# 5V-25V_to_12V3A_DC-DC_Converter.net
KiCad netlist of a schematic drawn in Altium Designer
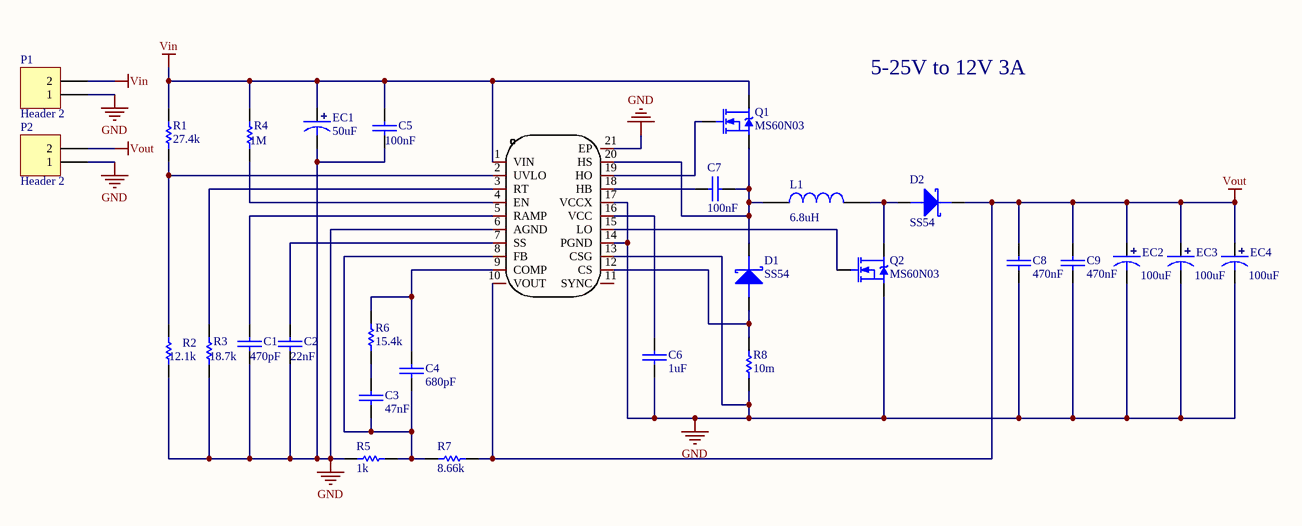
[diagram p0: 5V-25V to 12V3A DC-DC Converter.SchDoc]

(export (version "E")
  (design (tool "Eeschema 10.0.6"))
  (components
    (comp (ref "C1")
      (value "470pF")
      (footprint "0402C")
      (description "无极性电容")
      (libsource (lib "电容") (part "CAP"))
    )
    (comp (ref "C2")
      (value "22nF")
      (footprint "0402C")
      (description "无极性电容")
      (libsource (lib "电容") (part "CAP"))
    )
    (comp (ref "C3")
      (value "47nF")
      (footprint "0402C")
      (description "无极性电容")
      (libsource (lib "电容") (part "CAP"))
    )
    (comp (ref "C4")
      (value "680pF")
      (footprint "0402C")
      (description "无极性电容")
      (libsource (lib "电容") (part "CAP"))
    )
    (comp (ref "C5")
      (value "100nF")
      (footprint "0402C")
      (description "无极性电容")
      (libsource (lib "电容") (part "CAP"))
    )
    (comp (ref "C6")
      (value "1uF")
      (footprint "0402C")
      (description "无极性电容")
      (libsource (lib "电容") (part "CAP"))
    )
    (comp (ref "C7")
      (value "100nF")
      (footprint "0402C")
      (description "无极性电容")
      (libsource (lib "电容") (part "CAP"))
    )
    (comp (ref "C8")
      (value "470nF")
      (footprint "0402C")
      (description "无极性电容")
      (libsource (lib "电容") (part "CAP"))
    )
    (comp (ref "C9")
      (value "470nF")
      (footprint "0402C")
      (description "无极性电容")
      (libsource (lib "电容") (part "CAP"))
    )
    (comp (ref "D1")
      (value "SS54")
      (footprint "PCB库:肖特基二极管SS54")
      (description "肖特基二极管")
      (libsource (lib "二极管") (part "DIODE SCHOTTKY"))
    )
    (comp (ref "D2")
      (value "SS54")
      (footprint "PCB库:肖特基二极管SS54")
      (description "肖特基二极管")
      (libsource (lib "二极管") (part "DIODE SCHOTTKY"))
    )
    (comp (ref "EC1")
      (value "50uF")
      (footprint "SMD-EC6.3X6.3X10")
      (description "贴片电解电容")
      (libsource (lib "电容") (part "SMD_ECAP"))
    )
    (comp (ref "EC2")
      (value "100uF")
      (footprint "SMD-EC8X8X10")
      (description "贴片电解电容")
      (libsource (lib "电容") (part "SMD_ECAP"))
    )
    (comp (ref "EC3")
      (value "100uF")
      (footprint "SMD-EC8X8X10")
      (description "贴片电解电容")
      (libsource (lib "电容") (part "SMD_ECAP"))
    )
    (comp (ref "EC4")
      (value "100uF")
      (footprint "SMD-EC8X8X10")
      (description "贴片电解电容")
      (libsource (lib "电容") (part "SMD_ECAP"))
    )
    (comp (ref "L1")
      (value "6.8uH")
      (footprint "0630L")
      (description "INDUCTOR")
      (libsource (lib "电感") (part "INDUCTOR"))
    )
    (comp (ref "P1")
      (value "Header 2")
      (footprint "HDR1X2")
      (description "Header, 2-Pin")
      (fields (field (name "PUBLISHER") "Altium Limited"))
      (libsource (lib "Miscellaneous Connectors") (part "Header 2"))
    )
    (comp (ref "P2")
      (value "Header 2")
      (footprint "HDR1X2")
      (description "Header, 2-Pin")
      (fields (field (name "PUBLISHER") "Altium Limited"))
      (libsource (lib "Miscellaneous Connectors") (part "Header 2"))
    )
    (comp (ref "Q1")
      (value "MS60N03")
      (footprint "TO252")
      (description "N沟道场效应管")
      (libsource (lib "MOS管") (part "N-MOS"))
    )
    (comp (ref "Q2")
      (value "MS60N03")
      (footprint "TO252")
      (description "N沟道场效应管")
      (libsource (lib "MOS管") (part "N-MOS"))
    )
    (comp (ref "R1") (value "27.4k") (footprint "0402R") (libsource (lib "电阻") (part "RES")))
    (comp (ref "R2") (value "12.1k") (footprint "0402R") (libsource (lib "电阻") (part "RES")))
    (comp (ref "R3") (value "18.7k") (footprint "0402R") (libsource (lib "电阻") (part "RES")))
    (comp (ref "R4") (value "1M") (footprint "0402R") (libsource (lib "电阻") (part "RES")))
    (comp (ref "R5") (value "1k") (footprint "0402R") (libsource (lib "电阻") (part "RES")))
    (comp (ref "R6") (value "15.4k") (footprint "0402R") (libsource (lib "电阻") (part "RES")))
    (comp (ref "R7") (value "8.66k") (footprint "0402R") (libsource (lib "电阻") (part "RES")))
    (comp (ref "R8")
      (value "10m")
      (footprint "1206R")
      (description "P>0.2w")
      (libsource (lib "电阻") (part "RES"))
    )
    (comp (ref "U1")
      (value "LM25118MHX/NOPB")
      (footprint "PCB库:LM25118")
      (fields (field (name "MANUFACTURER") "TI(德州仪器)"))
      (libsource (lib "原理图库") (part "LM25118MHX/NOPB"))
    )
  )
  (nets
    (net (code "1") (name "GND") (class "Default")
      (node (ref "C1") (pin "1") (pinfunction "1_1") (pintype "passive"))
      (node (ref "C2") (pin "1") (pinfunction "1_1") (pintype "passive"))
      (node (ref "C5") (pin "1") (pinfunction "1_1") (pintype "passive"))
      (node (ref "C6") (pin "1") (pinfunction "1_1") (pintype "passive"))
      (node (ref "C8") (pin "2") (pinfunction "2_2") (pintype "passive"))
      (node (ref "C9") (pin "2") (pinfunction "2_2") (pintype "passive"))
      (node (ref "EC1") (pin "2") (pinfunction "2_2") (pintype "passive"))
      (node (ref "EC2") (pin "2") (pinfunction "2_2") (pintype "passive"))
      (node (ref "EC3") (pin "2") (pinfunction "2_2") (pintype "passive"))
      (node (ref "EC4") (pin "2") (pinfunction "2_2") (pintype "passive"))
      (node (ref "P1") (pin "1") (pinfunction "1_1") (pintype "passive"))
      (node (ref "P2") (pin "1") (pinfunction "1_1") (pintype "passive"))
      (node (ref "Q2") (pin "S") (pinfunction "S_S") (pintype "passive"))
      (node (ref "R2") (pin "1") (pinfunction "1_1") (pintype "passive"))
      (node (ref "R3") (pin "1") (pinfunction "1_1") (pintype "passive"))
      (node (ref "R5") (pin "1") (pinfunction "1_1") (pintype "passive"))
      (node (ref "R8") (pin "1") (pinfunction "1_1") (pintype "passive"))
      (node (ref "U1") (pin "13") (pinfunction "CSG_13") (pintype "passive"))
      (node (ref "U1") (pin "14") (pinfunction "PGND_14") (pintype "passive"))
      (node (ref "U1") (pin "17") (pinfunction "VCCX_17") (pintype "passive"))
      (node (ref "U1") (pin "21") (pinfunction "EP_21") (pintype "passive"))
      (node (ref "U1") (pin "6") (pinfunction "AGND_6") (pintype "passive"))
    )
    (net (code "2") (name "Net-(C3-Pad2)") (class "Default")
      (node (ref "C3") (pin "2") (pinfunction "2_2") (pintype "passive"))
      (node (ref "R6") (pin "1") (pinfunction "1_1") (pintype "passive"))
    )
    (net (code "3") (name "Net-(D2-Pad1)") (class "Default")
      (node (ref "D2") (pin "1") (pinfunction "1_1") (pintype "passive"))
      (node (ref "L1") (pin "2") (pinfunction "2_2") (pintype "passive"))
      (node (ref "Q2") (pin "D") (pinfunction "D_D") (pintype "passive"))
    )
    (net (code "4") (name "Net-(U1-COMP)") (class "Default")
      (node (ref "C4") (pin "2") (pinfunction "2_2") (pintype "passive"))
      (node (ref "R6") (pin "2") (pinfunction "2_2") (pintype "passive"))
      (node (ref "U1") (pin "9") (pinfunction "COMP_9") (pintype "passive"))
    )
    (net (code "5") (name "Net-(U1-CS)") (class "Default")
      (node (ref "D1") (pin "1") (pinfunction "1_1") (pintype "passive"))
      (node (ref "R8") (pin "2") (pinfunction "2_2") (pintype "passive"))
      (node (ref "U1") (pin "12") (pinfunction "CS_12") (pintype "passive"))
    )
    (net (code "6") (name "Net-(U1-EN)") (class "Default")
      (node (ref "R4") (pin "1") (pinfunction "1_1") (pintype "passive"))
      (node (ref "U1") (pin "4") (pinfunction "EN_4") (pintype "passive"))
    )
    (net (code "7") (name "Net-(U1-FB)") (class "Default")
      (node (ref "C3") (pin "1") (pinfunction "1_1") (pintype "passive"))
      (node (ref "C4") (pin "1") (pinfunction "1_1") (pintype "passive"))
      (node (ref "R5") (pin "2") (pinfunction "2_2") (pintype "passive"))
      (node (ref "R7") (pin "2") (pinfunction "2_2") (pintype "passive"))
      (node (ref "U1") (pin "8") (pinfunction "FB_8") (pintype "passive"))
    )
    (net (code "8") (name "Net-(U1-HB)") (class "Default")
      (node (ref "C7") (pin "2") (pinfunction "2_2") (pintype "passive"))
      (node (ref "U1") (pin "18") (pinfunction "HB_18") (pintype "passive"))
    )
    (net (code "9") (name "Net-(U1-HO)") (class "Default")
      (node (ref "Q1") (pin "G") (pinfunction "G_G") (pintype "passive"))
      (node (ref "U1") (pin "19") (pinfunction "HO_19") (pintype "passive"))
    )
    (net (code "10") (name "Net-(U1-HS)") (class "Default")
      (node (ref "C7") (pin "1") (pinfunction "1_1") (pintype "passive"))
      (node (ref "D1") (pin "2") (pinfunction "2_2") (pintype "passive"))
      (node (ref "L1") (pin "1") (pinfunction "1_1") (pintype "passive"))
      (node (ref "Q1") (pin "S") (pinfunction "S_S") (pintype "passive"))
      (node (ref "U1") (pin "20") (pinfunction "HS_20") (pintype "passive"))
    )
    (net (code "11") (name "Net-(U1-LO)") (class "Default")
      (node (ref "Q2") (pin "G") (pinfunction "G_G") (pintype "passive"))
      (node (ref "U1") (pin "15") (pinfunction "LO_15") (pintype "passive"))
    )
    (net (code "12") (name "Net-(U1-RAMP)") (class "Default")
      (node (ref "C1") (pin "2") (pinfunction "2_2") (pintype "passive"))
      (node (ref "U1") (pin "5") (pinfunction "RAMP_5") (pintype "passive"))
    )
    (net (code "13") (name "Net-(U1-RT)") (class "Default")
      (node (ref "R3") (pin "2") (pinfunction "2_2") (pintype "passive"))
      (node (ref "U1") (pin "3") (pinfunction "RT_3") (pintype "passive"))
    )
    (net (code "14") (name "Net-(U1-SS)") (class "Default")
      (node (ref "C2") (pin "2") (pinfunction "2_2") (pintype "passive"))
      (node (ref "U1") (pin "7") (pinfunction "SS_7") (pintype "passive"))
    )
    (net (code "15") (name "Net-(U1-UVLO)") (class "Default")
      (node (ref "R1") (pin "1") (pinfunction "1_1") (pintype "passive"))
      (node (ref "R2") (pin "2") (pinfunction "2_2") (pintype "passive"))
      (node (ref "U1") (pin "2") (pinfunction "UVLO_2") (pintype "passive"))
    )
    (net (code "16") (name "Net-(U1-VCC)") (class "Default")
      (node (ref "C6") (pin "2") (pinfunction "2_2") (pintype "passive"))
      (node (ref "U1") (pin "16") (pinfunction "VCC_16") (pintype "passive"))
    )
    (net (code "17") (name "Vin") (class "Default")
      (node (ref "C5") (pin "2") (pinfunction "2_2") (pintype "passive"))
      (node (ref "EC1") (pin "1") (pinfunction "1_1") (pintype "passive"))
      (node (ref "P1") (pin "2") (pinfunction "2_2") (pintype "passive"))
      (node (ref "Q1") (pin "D") (pinfunction "D_D") (pintype "passive"))
      (node (ref "R1") (pin "2") (pinfunction "2_2") (pintype "passive"))
      (node (ref "R4") (pin "2") (pinfunction "2_2") (pintype "passive"))
      (node (ref "U1") (pin "1") (pinfunction "VIN_1") (pintype "passive"))
    )
    (net (code "18") (name "Vout") (class "Default")
      (node (ref "C8") (pin "1") (pinfunction "1_1") (pintype "passive"))
      (node (ref "C9") (pin "1") (pinfunction "1_1") (pintype "passive"))
      (node (ref "D2") (pin "2") (pinfunction "2_2") (pintype "passive"))
      (node (ref "EC2") (pin "1") (pinfunction "1_1") (pintype "passive"))
      (node (ref "EC3") (pin "1") (pinfunction "1_1") (pintype "passive"))
      (node (ref "EC4") (pin "1") (pinfunction "1_1") (pintype "passive"))
      (node (ref "P2") (pin "2") (pinfunction "2_2") (pintype "passive"))
      (node (ref "R7") (pin "1") (pinfunction "1_1") (pintype "passive"))
      (node (ref "U1") (pin "10") (pinfunction "VOUT_10") (pintype "passive"))
    )
    (net (code "19") (name "unconnected-(U1-SYNC-Pad11)") (class "Default")
      (node (ref "U1") (pin "11") (pinfunction "SYNC_11") (pintype "passive"))
    )
  )
)
